# peripheral2.net
KiCad netlist of a schematic drawn in EAGLE
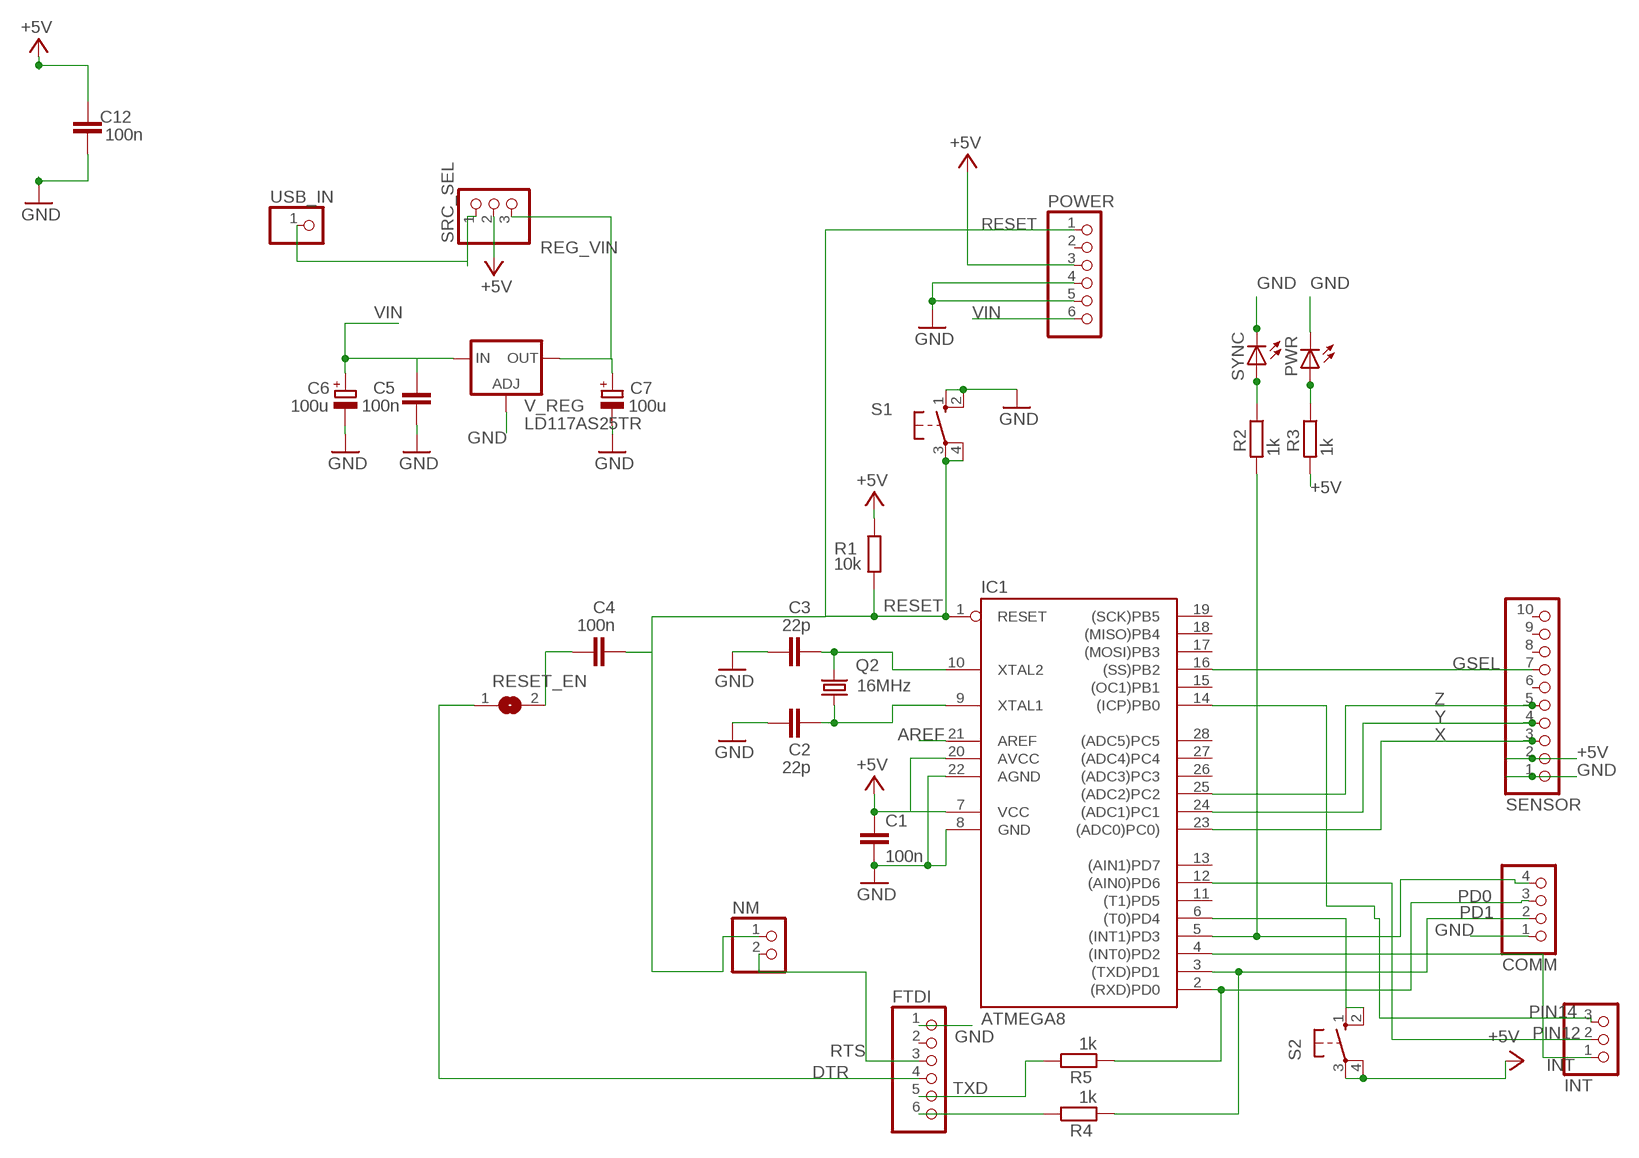
[diagram p0: schematic, sheet 1]

(export (version "E")
  (design (tool "Eeschema 10.0.6"))
  (components
    (comp (ref "C1")
      (value "100n")
      (footprint "eagle-import:C1206")
      (libsource (lib "eagle-import") (part "C-EUC1206"))
    )
    (comp (ref "C2")
      (value "22p")
      (footprint "eagle-import:C1206")
      (libsource (lib "eagle-import") (part "C-EUC1206"))
    )
    (comp (ref "C3")
      (value "22p")
      (footprint "eagle-import:C1206")
      (libsource (lib "eagle-import") (part "C-EUC1206"))
    )
    (comp (ref "C4")
      (value "100n")
      (footprint "eagle-import:C1206")
      (libsource (lib "eagle-import") (part "C-EUC1206"))
    )
    (comp (ref "C5")
      (value "100n")
      (footprint "eagle-import:C1206")
      (libsource (lib "eagle-import") (part "C-EUC1206"))
    )
    (comp (ref "C6")
      (value "100u")
      (footprint "eagle-import:PANASONIC_D")
      (libsource (lib "eagle-import") (part "CPOL-EUD"))
    )
    (comp (ref "C7")
      (value "100u")
      (footprint "eagle-import:PANASONIC_D")
      (libsource (lib "eagle-import") (part "CPOL-EUD"))
    )
    (comp (ref "C12")
      (value "100n")
      (footprint "eagle-import:C1206")
      (libsource (lib "eagle-import") (part "C-EUC1206"))
    )
    (comp (ref "COMM")
      (value "PINHD-1X4")
      (footprint "eagle-import:1X04")
      (libsource (lib "eagle-import") (part "PINHD-1X4"))
    )
    (comp (ref "FTDI")
      (value "PINHD-1X6")
      (footprint "eagle-import:1X06")
      (libsource (lib "eagle-import") (part "PINHD-1X6"))
    )
    (comp (ref "IC1")
      (value "ATMEGA8")
      (footprint "eagle-import:DIL28-3")
      (libsource (lib "eagle-import") (part "AT90S4433P"))
    )
    (comp (ref "INT")
      (value "PINHD-1X3")
      (footprint "eagle-import:1X03")
      (libsource (lib "eagle-import") (part "PINHD-1X3"))
    )
    (comp (ref "NM")
      (value "PINHD-1X2")
      (footprint "eagle-import:1X02")
      (libsource (lib "eagle-import") (part "PINHD-1X2"))
    )
    (comp (ref "POWER")
      (value "PINHD-1X6")
      (footprint "eagle-import:1X06")
      (libsource (lib "eagle-import") (part "PINHD-1X6"))
    )
    (comp (ref "PWR")
      (value "LEDCHIPLED_1206")
      (footprint "eagle-import:CHIPLED_1206")
      (libsource (lib "eagle-import") (part "LEDCHIPLED_1206"))
    )
    (comp (ref "Q2")
      (value "16MHz")
      (footprint "eagle-import:HC49_S")
      (libsource (lib "eagle-import") (part "CRYTALHC49S"))
    )
    (comp (ref "R1")
      (value "10k")
      (footprint "eagle-import:R1206")
      (libsource (lib "eagle-import") (part "R-EU_R1206"))
    )
    (comp (ref "R2")
      (value "1k")
      (footprint "eagle-import:R1206")
      (libsource (lib "eagle-import") (part "R-EU_R1206"))
    )
    (comp (ref "R3")
      (value "1k")
      (footprint "eagle-import:R1206")
      (libsource (lib "eagle-import") (part "R-EU_R1206"))
    )
    (comp (ref "R4")
      (value "1k")
      (footprint "eagle-import:R1206")
      (libsource (lib "eagle-import") (part "R-EU_R1206"))
    )
    (comp (ref "R5")
      (value "1k")
      (footprint "eagle-import:R1206")
      (libsource (lib "eagle-import") (part "R-EU_R1206"))
    )
    (comp (ref "RESET_EN")
      (value "SJ")
      (footprint "eagle-import:SJ")
      (libsource (lib "eagle-import") (part "SJ"))
    )
    (comp (ref "S1")
      (value "10-XX")
      (footprint "eagle-import:B3F-10XX")
      (fields (field (name "MPN") "B3F-1000"))
      (libsource (lib "eagle-import") (part "10-XX"))
    )
    (comp (ref "S2")
      (value "10-XX")
      (footprint "eagle-import:B3F-10XX")
      (fields (field (name "MPN") "B3F-1000"))
      (libsource (lib "eagle-import") (part "10-XX"))
    )
    (comp (ref "SENSOR")
      (value "PINHD-1X10")
      (footprint "eagle-import:1X10")
      (libsource (lib "eagle-import") (part "PINHD-1X10"))
    )
    (comp (ref "SRC_SEL")
      (value "PINHD-1X3")
      (footprint "eagle-import:1X03")
      (libsource (lib "eagle-import") (part "PINHD-1X3"))
    )
    (comp (ref "SYNC")
      (value "LEDCHIPLED_1206")
      (footprint "eagle-import:CHIPLED_1206")
      (libsource (lib "eagle-import") (part "LEDCHIPLED_1206"))
    )
    (comp (ref "USB_IN")
      (value "PINHD-1X1")
      (footprint "eagle-import:1X01")
      (libsource (lib "eagle-import") (part "PINHD-1X1"))
    )
    (comp (ref "V_REG")
      (value "LD117AS25TR")
      (footprint "eagle-import:SOT223")
      (libsource (lib "eagle-import") (part "LD117A?S25TR"))
    )
  )
  (nets
    (net (code "1") (name "+5V") (class "Default")
      (node (ref "C1") (pin "1") (pinfunction "1_1") (pintype "passive"))
      (node (ref "C12") (pin "2") (pinfunction "2_2") (pintype "passive"))
      (node (ref "IC1") (pin "20") (pinfunction "AVCC_20") (pintype "power_in"))
      (node (ref "IC1") (pin "7") (pinfunction "VCC_7") (pintype "power_in"))
      (node (ref "POWER") (pin "3") (pinfunction "3_3") (pintype "passive"))
      (node (ref "R1") (pin "2") (pinfunction "2_2") (pintype "passive"))
      (node (ref "R3") (pin "2") (pinfunction "2_2") (pintype "passive"))
      (node (ref "S2") (pin "3") (pinfunction "P_3") (pintype "passive"))
      (node (ref "S2") (pin "4") (pinfunction "P1_4") (pintype "passive"))
      (node (ref "SENSOR") (pin "2") (pinfunction "2_2") (pintype "passive"))
      (node (ref "SRC_SEL") (pin "2") (pinfunction "2_2") (pintype "passive"))
    )
    (net (code "2") (name "/AREF") (class "Default")
      (node (ref "IC1") (pin "21") (pinfunction "AREF_21") (pintype "power_in"))
    )
    (net (code "3") (name "/DTR") (class "Default")
      (node (ref "FTDI") (pin "4") (pinfunction "4_4") (pintype "passive"))
      (node (ref "RESET_EN") (pin "1") (pinfunction "1_1") (pintype "passive"))
    )
    (net (code "4") (name "/GSEL") (class "Default")
      (node (ref "IC1") (pin "16") (pinfunction "(SS)PB2_16") (pintype "bidirectional"))
      (node (ref "SENSOR") (pin "7") (pinfunction "7_7") (pintype "passive"))
    )
    (net (code "5") (name "/INT") (class "Default")
      (node (ref "IC1") (pin "4") (pinfunction "(INT0)PD2_4") (pintype "bidirectional"))
      (node (ref "INT") (pin "1") (pinfunction "1_1") (pintype "passive"))
    )
    (net (code "6") (name "/PD0") (class "Default")
      (node (ref "COMM") (pin "3") (pinfunction "3_3") (pintype "passive"))
      (node (ref "IC1") (pin "2") (pinfunction "(RXD)PD0_2") (pintype "bidirectional"))
      (node (ref "R5") (pin "2") (pinfunction "2_2") (pintype "passive"))
    )
    (net (code "7") (name "/PD1") (class "Default")
      (node (ref "COMM") (pin "2") (pinfunction "2_2") (pintype "passive"))
      (node (ref "IC1") (pin "3") (pinfunction "(TXD)PD1_3") (pintype "bidirectional"))
      (node (ref "R4") (pin "2") (pinfunction "2_2") (pintype "passive"))
    )
    (net (code "8") (name "/PIN12") (class "Default")
      (node (ref "IC1") (pin "12") (pinfunction "(AIN0)PD6_12") (pintype "bidirectional"))
      (node (ref "INT") (pin "2") (pinfunction "2_2") (pintype "passive"))
    )
    (net (code "9") (name "/PIN14") (class "Default")
      (node (ref "IC1") (pin "14") (pinfunction "(ICP)PB0_14") (pintype "bidirectional"))
      (node (ref "INT") (pin "3") (pinfunction "3_3") (pintype "passive"))
    )
    (net (code "10") (name "/REG_VIN") (class "Default")
      (node (ref "C7") (pin "+") (pinfunction "+_+") (pintype "passive"))
      (node (ref "SRC_SEL") (pin "3") (pinfunction "3_3") (pintype "passive"))
      (node (ref "V_REG") (pin "4") (pinfunction "OUT_4") (pintype "passive"))
    )
    (net (code "11") (name "/RESET") (class "Default")
      (node (ref "C4") (pin "2") (pinfunction "2_2") (pintype "passive"))
      (node (ref "IC1") (pin "1") (pinfunction "RESET_1") (pintype "input"))
      (node (ref "NM") (pin "1") (pinfunction "1_1") (pintype "passive"))
      (node (ref "POWER") (pin "1") (pinfunction "1_1") (pintype "passive"))
      (node (ref "R1") (pin "1") (pinfunction "1_1") (pintype "passive"))
      (node (ref "S1") (pin "3") (pinfunction "P_3") (pintype "passive"))
      (node (ref "S1") (pin "4") (pinfunction "P1_4") (pintype "passive"))
    )
    (net (code "12") (name "/RTS") (class "Default")
      (node (ref "FTDI") (pin "3") (pinfunction "3_3") (pintype "passive"))
      (node (ref "NM") (pin "2") (pinfunction "2_2") (pintype "passive"))
    )
    (net (code "13") (name "/TXD") (class "Default")
      (node (ref "FTDI") (pin "5") (pinfunction "5_5") (pintype "passive"))
      (node (ref "R5") (pin "1") (pinfunction "1_1") (pintype "passive"))
    )
    (net (code "14") (name "/VIN") (class "Default")
      (node (ref "C5") (pin "2") (pinfunction "2_2") (pintype "passive"))
      (node (ref "C6") (pin "+") (pinfunction "+_+") (pintype "passive"))
      (node (ref "POWER") (pin "6") (pinfunction "6_6") (pintype "passive"))
      (node (ref "V_REG") (pin "3") (pinfunction "IN_3") (pintype "input"))
    )
    (net (code "15") (name "/X") (class "Default")
      (node (ref "IC1") (pin "23") (pinfunction "(ADC0)PC0)_23") (pintype "bidirectional"))
      (node (ref "SENSOR") (pin "3") (pinfunction "3_3") (pintype "passive"))
    )
    (net (code "16") (name "/Y") (class "Default")
      (node (ref "IC1") (pin "24") (pinfunction "(ADC1)PC1_24") (pintype "bidirectional"))
      (node (ref "SENSOR") (pin "4") (pinfunction "4_4") (pintype "passive"))
    )
    (net (code "17") (name "/Z") (class "Default")
      (node (ref "IC1") (pin "25") (pinfunction "(ADC2)PC2_25") (pintype "bidirectional"))
      (node (ref "SENSOR") (pin "5") (pinfunction "5_5") (pintype "passive"))
    )
    (net (code "18") (name "GND") (class "Default")
      (node (ref "C1") (pin "2") (pinfunction "2_2") (pintype "passive"))
      (node (ref "C12") (pin "1") (pinfunction "1_1") (pintype "passive"))
      (node (ref "C2") (pin "1") (pinfunction "1_1") (pintype "passive"))
      (node (ref "C3") (pin "1") (pinfunction "1_1") (pintype "passive"))
      (node (ref "C5") (pin "1") (pinfunction "1_1") (pintype "passive"))
      (node (ref "C6") (pin "-") (pinfunction "-_-") (pintype "passive"))
      (node (ref "C7") (pin "-") (pinfunction "-_-") (pintype "passive"))
      (node (ref "COMM") (pin "1") (pinfunction "1_1") (pintype "passive"))
      (node (ref "FTDI") (pin "1") (pinfunction "1_1") (pintype "passive"))
      (node (ref "IC1") (pin "22") (pinfunction "AGND_22") (pintype "power_in"))
      (node (ref "IC1") (pin "8") (pinfunction "GND_8") (pintype "power_in"))
      (node (ref "POWER") (pin "4") (pinfunction "4_4") (pintype "passive"))
      (node (ref "POWER") (pin "5") (pinfunction "5_5") (pintype "passive"))
      (node (ref "PWR") (pin "C") (pinfunction "C_C") (pintype "passive"))
      (node (ref "S1") (pin "1") (pinfunction "S_1") (pintype "passive"))
      (node (ref "S1") (pin "2") (pinfunction "S1_2") (pintype "passive"))
      (node (ref "SENSOR") (pin "1") (pinfunction "1_1") (pintype "passive"))
      (node (ref "SYNC") (pin "C") (pinfunction "C_C") (pintype "passive"))
      (node (ref "V_REG") (pin "1") (pinfunction "ADJ_1") (pintype "input"))
    )
    (net (code "19") (name "Net-(C4-Pad1)") (class "Default")
      (node (ref "C4") (pin "1") (pinfunction "1_1") (pintype "passive"))
      (node (ref "RESET_EN") (pin "2") (pinfunction "2_2") (pintype "passive"))
    )
    (net (code "20") (name "Net-(FTDI-Pad6)") (class "Default")
      (node (ref "FTDI") (pin "6") (pinfunction "6_6") (pintype "passive"))
      (node (ref "R4") (pin "1") (pinfunction "1_1") (pintype "passive"))
    )
    (net (code "21") (name "Net-(IC1-(INT1)PD3)") (class "Default")
      (node (ref "COMM") (pin "4") (pinfunction "4_4") (pintype "passive"))
      (node (ref "IC1") (pin "5") (pinfunction "(INT1)PD3_5") (pintype "bidirectional"))
      (node (ref "R2") (pin "2") (pinfunction "2_2") (pintype "passive"))
    )
    (net (code "22") (name "Net-(IC1-(T0)PD4)") (class "Default")
      (node (ref "IC1") (pin "6") (pinfunction "(T0)PD4_6") (pintype "bidirectional"))
      (node (ref "S2") (pin "1") (pinfunction "S_1") (pintype "passive"))
      (node (ref "S2") (pin "2") (pinfunction "S1_2") (pintype "passive"))
    )
    (net (code "23") (name "Net-(IC1-XTAL1)") (class "Default")
      (node (ref "C2") (pin "2") (pinfunction "2_2") (pintype "passive"))
      (node (ref "IC1") (pin "9") (pinfunction "XTAL1_9") (pintype "bidirectional"))
      (node (ref "Q2") (pin "1") (pinfunction "1_1") (pintype "passive"))
    )
    (net (code "24") (name "Net-(IC1-XTAL2)") (class "Default")
      (node (ref "C3") (pin "2") (pinfunction "2_2") (pintype "passive"))
      (node (ref "IC1") (pin "10") (pinfunction "XTAL2_10") (pintype "bidirectional"))
      (node (ref "Q2") (pin "2") (pinfunction "2_2") (pintype "passive"))
    )
    (net (code "25") (name "Net-(PWR-PadA)") (class "Default")
      (node (ref "PWR") (pin "A") (pinfunction "A_A") (pintype "passive"))
      (node (ref "R3") (pin "1") (pinfunction "1_1") (pintype "passive"))
    )
    (net (code "26") (name "Net-(R2-Pad1)") (class "Default")
      (node (ref "R2") (pin "1") (pinfunction "1_1") (pintype "passive"))
      (node (ref "SYNC") (pin "A") (pinfunction "A_A") (pintype "passive"))
    )
    (net (code "27") (name "Net-(SRC_SEL-Pad1)") (class "Default")
      (node (ref "SRC_SEL") (pin "1") (pinfunction "1_1") (pintype "passive"))
      (node (ref "USB_IN") (pin "1") (pinfunction "1_1") (pintype "passive"))
    )
    (net (code "28") (name "unconnected-(FTDI-Pad2)") (class "Default")
      (node (ref "FTDI") (pin "2") (pinfunction "2_2") (pintype "passive"))
    )
    (net (code "29") (name "unconnected-(IC1-(ADC3)PC3-Pad26)") (class "Default")
      (node (ref "IC1") (pin "26") (pinfunction "(ADC3)PC3_26") (pintype "bidirectional"))
    )
    (net (code "30") (name "unconnected-(IC1-(ADC4)PC4-Pad27)") (class "Default")
      (node (ref "IC1") (pin "27") (pinfunction "(ADC4)PC4_27") (pintype "bidirectional"))
    )
    (net (code "31") (name "unconnected-(IC1-(ADC5)PC5-Pad28)") (class "Default")
      (node (ref "IC1") (pin "28") (pinfunction "(ADC5)PC5_28") (pintype "bidirectional"))
    )
    (net (code "32") (name "unconnected-(IC1-(AIN1)PD7-Pad13)") (class "Default")
      (node (ref "IC1") (pin "13") (pinfunction "(AIN1)PD7_13") (pintype "bidirectional"))
    )
    (net (code "33") (name "unconnected-(IC1-(MISO)PB4-Pad18)") (class "Default")
      (node (ref "IC1") (pin "18") (pinfunction "(MISO)PB4_18") (pintype "bidirectional"))
    )
    (net (code "34") (name "unconnected-(IC1-(MOSI)PB3-Pad17)") (class "Default")
      (node (ref "IC1") (pin "17") (pinfunction "(MOSI)PB3_17") (pintype "bidirectional"))
    )
    (net (code "35") (name "unconnected-(IC1-(OC1)PB1-Pad15)") (class "Default")
      (node (ref "IC1") (pin "15") (pinfunction "(OC1)PB1_15") (pintype "bidirectional"))
    )
    (net (code "36") (name "unconnected-(IC1-(SCK)PB5-Pad19)") (class "Default")
      (node (ref "IC1") (pin "19") (pinfunction "(SCK)PB5_19") (pintype "bidirectional"))
    )
    (net (code "37") (name "unconnected-(IC1-(T1)PD5-Pad11)") (class "Default")
      (node (ref "IC1") (pin "11") (pinfunction "(T1)PD5_11") (pintype "bidirectional"))
    )
    (net (code "38") (name "unconnected-(POWER-Pad2)") (class "Default")
      (node (ref "POWER") (pin "2") (pinfunction "2_2") (pintype "passive"))
    )
    (net (code "39") (name "unconnected-(SENSOR-Pad6)") (class "Default")
      (node (ref "SENSOR") (pin "6") (pinfunction "6_6") (pintype "passive"))
    )
    (net (code "40") (name "unconnected-(SENSOR-Pad8)") (class "Default")
      (node (ref "SENSOR") (pin "8") (pinfunction "8_8") (pintype "passive"))
    )
    (net (code "41") (name "unconnected-(SENSOR-Pad9)") (class "Default")
      (node (ref "SENSOR") (pin "9") (pinfunction "9_9") (pintype "passive"))
    )
    (net (code "42") (name "unconnected-(SENSOR-Pad10)") (class "Default")
      (node (ref "SENSOR") (pin "10") (pinfunction "10_10") (pintype "passive"))
    )
  )
)
